# Leds.net
KiCad netlist of a schematic drawn in Altium Designer
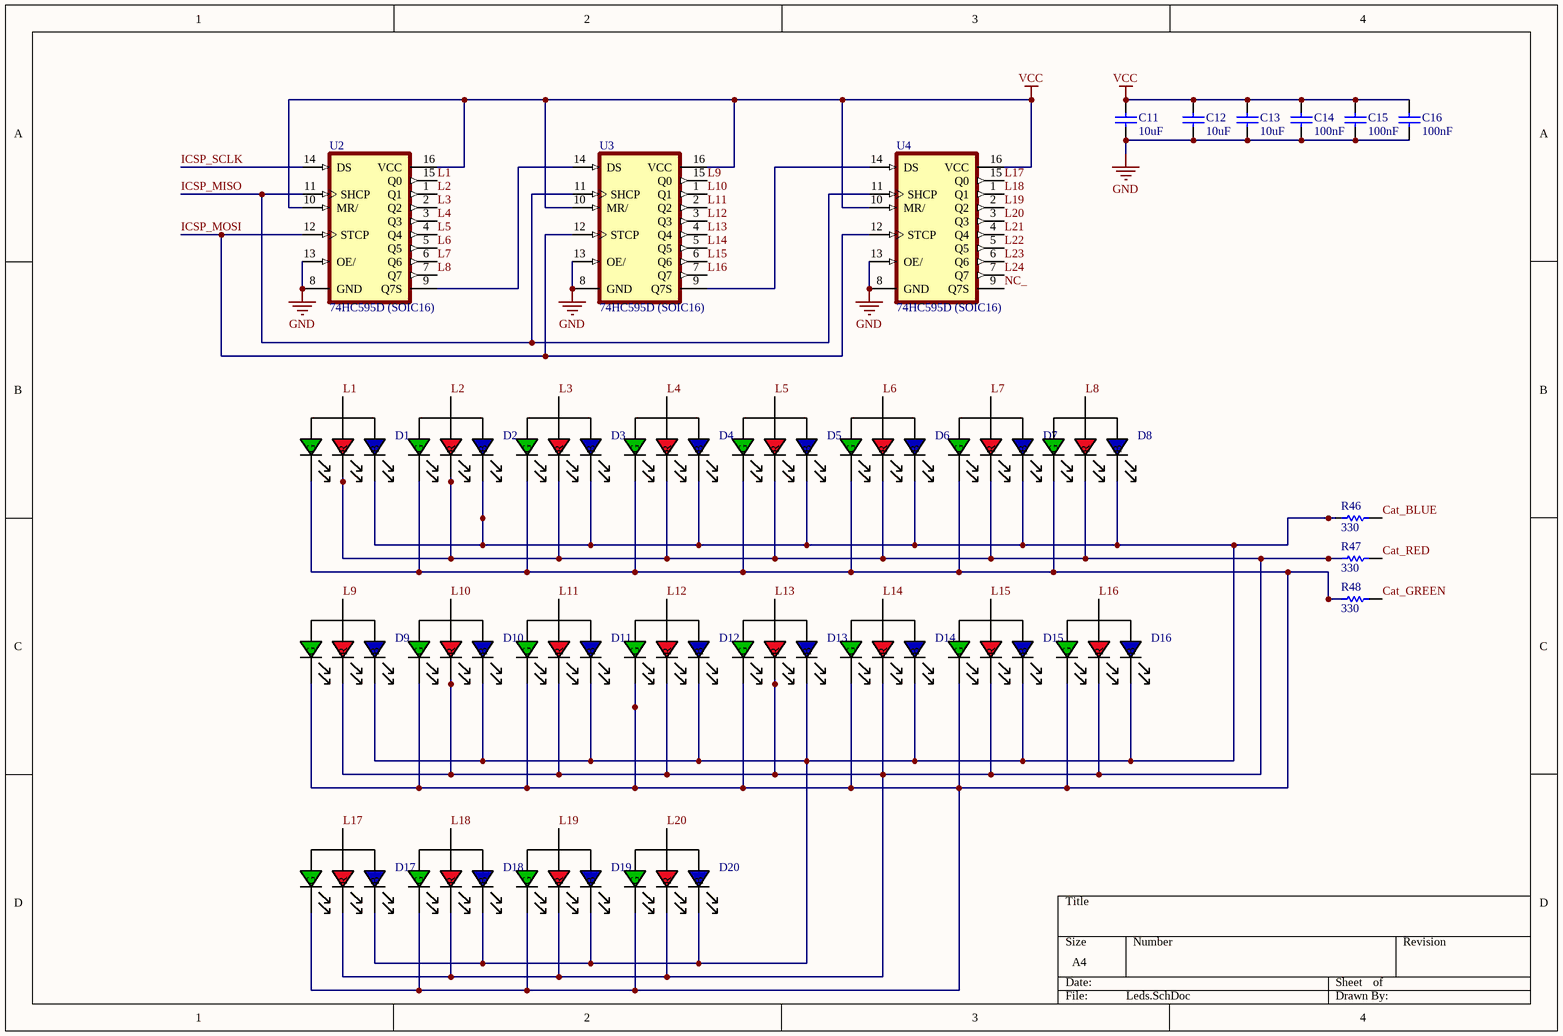
[diagram p0: Leds.SchDoc]

(export (version "E")
  (design (tool "Eeschema 10.0.6"))
  (components
    (comp (ref "C11")
      (value "10uF")
      (footprint "0603")
      (libsource (lib "LibDevs") (part "CAP 10uF 6.3V 20% 0603"))
    )
    (comp (ref "C12")
      (value "10uF")
      (footprint "0603")
      (libsource (lib "LibDevs") (part "CAP 10uF 6.3V 20% 0603"))
    )
    (comp (ref "C13")
      (value "10uF")
      (footprint "0603")
      (libsource (lib "LibDevs") (part "CAP 10uF 6.3V 20% 0603"))
    )
    (comp (ref "C14")
      (value "100nF")
      (footprint "0603")
      (libsource (lib "LibDevs") (part "CAP 100nF 10% 0603"))
    )
    (comp (ref "C15")
      (value "100nF")
      (footprint "0603")
      (libsource (lib "LibDevs") (part "CAP 100nF 10% 0603"))
    )
    (comp (ref "C16")
      (value "100nF")
      (footprint "0603")
      (libsource (lib "LibDevs") (part "CAP 100nF 10% 0603"))
    )
    (comp (ref "D1")
      (value "RGB LED CLEAR")
      (footprint "RADIAL 4 LEADS")
      (fields (field (name "MFR PART #") "TJ-L5FYTXHTCYLCRGB-AR") (field (name "LCSC PART #") "C330749"))
      (libsource (lib "LibDevs") (part "LED RGB TJ-L5FYTXHTCYLCRGB-AR"))
    )
    (comp (ref "D2")
      (value "RGB LED CLEAR")
      (footprint "RADIAL 4 LEADS")
      (fields (field (name "MFR PART #") "TJ-L5FYTXHTCYLCRGB-AR") (field (name "LCSC PART #") "C330749"))
      (libsource (lib "LibDevs") (part "LED RGB TJ-L5FYTXHTCYLCRGB-AR"))
    )
    (comp (ref "D3")
      (value "RGB LED CLEAR")
      (footprint "RADIAL 4 LEADS")
      (fields (field (name "MFR PART #") "TJ-L5FYTXHTCYLCRGB-AR") (field (name "LCSC PART #") "C330749"))
      (libsource (lib "LibDevs") (part "LED RGB TJ-L5FYTXHTCYLCRGB-AR"))
    )
    (comp (ref "D4")
      (value "RGB LED CLEAR")
      (footprint "RADIAL 4 LEADS")
      (fields (field (name "MFR PART #") "TJ-L5FYTXHTCYLCRGB-AR") (field (name "LCSC PART #") "C330749"))
      (libsource (lib "LibDevs") (part "LED RGB TJ-L5FYTXHTCYLCRGB-AR"))
    )
    (comp (ref "D5")
      (value "RGB LED CLEAR")
      (footprint "RADIAL 4 LEADS")
      (fields (field (name "MFR PART #") "TJ-L5FYTXHTCYLCRGB-AR") (field (name "LCSC PART #") "C330749"))
      (libsource (lib "LibDevs") (part "LED RGB TJ-L5FYTXHTCYLCRGB-AR"))
    )
    (comp (ref "D6")
      (value "RGB LED CLEAR")
      (footprint "RADIAL 4 LEADS")
      (fields (field (name "MFR PART #") "TJ-L5FYTXHTCYLCRGB-AR") (field (name "LCSC PART #") "C330749"))
      (libsource (lib "LibDevs") (part "LED RGB TJ-L5FYTXHTCYLCRGB-AR"))
    )
    (comp (ref "D7")
      (value "RGB LED CLEAR")
      (footprint "RADIAL 4 LEADS")
      (fields (field (name "MFR PART #") "TJ-L5FYTXHTCYLCRGB-AR") (field (name "LCSC PART #") "C330749"))
      (libsource (lib "LibDevs") (part "LED RGB TJ-L5FYTXHTCYLCRGB-AR"))
    )
    (comp (ref "D8")
      (value "RGB LED CLEAR")
      (footprint "RADIAL 4 LEADS")
      (fields (field (name "MFR PART #") "TJ-L5FYTXHTCYLCRGB-AR") (field (name "LCSC PART #") "C330749"))
      (libsource (lib "LibDevs") (part "LED RGB TJ-L5FYTXHTCYLCRGB-AR"))
    )
    (comp (ref "D9")
      (value "RGB LED CLEAR")
      (footprint "RADIAL 4 LEADS")
      (fields (field (name "MFR PART #") "TJ-L5FYTXHTCYLCRGB-AR") (field (name "LCSC PART #") "C330749"))
      (libsource (lib "LibDevs") (part "LED RGB TJ-L5FYTXHTCYLCRGB-AR"))
    )
    (comp (ref "D10")
      (value "RGB LED CLEAR")
      (footprint "RADIAL 4 LEADS")
      (fields (field (name "MFR PART #") "TJ-L5FYTXHTCYLCRGB-AR") (field (name "LCSC PART #") "C330749"))
      (libsource (lib "LibDevs") (part "LED RGB TJ-L5FYTXHTCYLCRGB-AR"))
    )
    (comp (ref "D11")
      (value "RGB LED CLEAR")
      (footprint "RADIAL 4 LEADS")
      (fields (field (name "MFR PART #") "TJ-L5FYTXHTCYLCRGB-AR") (field (name "LCSC PART #") "C330749"))
      (libsource (lib "LibDevs") (part "LED RGB TJ-L5FYTXHTCYLCRGB-AR"))
    )
    (comp (ref "D12")
      (value "RGB LED CLEAR")
      (footprint "RADIAL 4 LEADS")
      (fields (field (name "MFR PART #") "TJ-L5FYTXHTCYLCRGB-AR") (field (name "LCSC PART #") "C330749"))
      (libsource (lib "LibDevs") (part "LED RGB TJ-L5FYTXHTCYLCRGB-AR"))
    )
    (comp (ref "D13")
      (value "RGB LED CLEAR")
      (footprint "RADIAL 4 LEADS")
      (fields (field (name "MFR PART #") "TJ-L5FYTXHTCYLCRGB-AR") (field (name "LCSC PART #") "C330749"))
      (libsource (lib "LibDevs") (part "LED RGB TJ-L5FYTXHTCYLCRGB-AR"))
    )
    (comp (ref "D14")
      (value "RGB LED CLEAR")
      (footprint "RADIAL 4 LEADS")
      (fields (field (name "MFR PART #") "TJ-L5FYTXHTCYLCRGB-AR") (field (name "LCSC PART #") "C330749"))
      (libsource (lib "LibDevs") (part "LED RGB TJ-L5FYTXHTCYLCRGB-AR"))
    )
    (comp (ref "D15")
      (value "RGB LED CLEAR")
      (footprint "RADIAL 4 LEADS")
      (fields (field (name "MFR PART #") "TJ-L5FYTXHTCYLCRGB-AR") (field (name "LCSC PART #") "C330749"))
      (libsource (lib "LibDevs") (part "LED RGB TJ-L5FYTXHTCYLCRGB-AR"))
    )
    (comp (ref "D16")
      (value "RGB LED CLEAR")
      (footprint "RADIAL 4 LEADS")
      (fields (field (name "MFR PART #") "TJ-L5FYTXHTCYLCRGB-AR") (field (name "LCSC PART #") "C330749"))
      (libsource (lib "LibDevs") (part "LED RGB TJ-L5FYTXHTCYLCRGB-AR"))
    )
    (comp (ref "D17")
      (value "RGB LED CLEAR")
      (footprint "RADIAL 4 LEADS")
      (fields (field (name "MFR PART #") "TJ-L5FYTXHTCYLCRGB-AR") (field (name "LCSC PART #") "C330749"))
      (libsource (lib "LibDevs") (part "LED RGB TJ-L5FYTXHTCYLCRGB-AR"))
    )
    (comp (ref "D18")
      (value "RGB LED CLEAR")
      (footprint "RADIAL 4 LEADS")
      (fields (field (name "MFR PART #") "TJ-L5FYTXHTCYLCRGB-AR") (field (name "LCSC PART #") "C330749"))
      (libsource (lib "LibDevs") (part "LED RGB TJ-L5FYTXHTCYLCRGB-AR"))
    )
    (comp (ref "D19")
      (value "RGB LED CLEAR")
      (footprint "RADIAL 4 LEADS")
      (fields (field (name "MFR PART #") "TJ-L5FYTXHTCYLCRGB-AR") (field (name "LCSC PART #") "C330749"))
      (libsource (lib "LibDevs") (part "LED RGB TJ-L5FYTXHTCYLCRGB-AR"))
    )
    (comp (ref "D20")
      (value "RGB LED CLEAR")
      (footprint "RADIAL 4 LEADS")
      (fields (field (name "MFR PART #") "TJ-L5FYTXHTCYLCRGB-AR") (field (name "LCSC PART #") "C330749"))
      (libsource (lib "LibDevs") (part "LED RGB TJ-L5FYTXHTCYLCRGB-AR"))
    )
    (comp (ref "R46")
      (value "330")
      (footprint "0603")
      (fields (field (name "Comment") "RESISTOR GENERIC"))
      (libsource (lib "LibDevs") (part "RESISTOR GENERIC"))
    )
    (comp (ref "R47")
      (value "330")
      (footprint "0603")
      (fields (field (name "Comment") "RESISTOR GENERIC"))
      (libsource (lib "LibDevs") (part "RESISTOR GENERIC"))
    )
    (comp (ref "R48")
      (value "330")
      (footprint "0603")
      (fields (field (name "Comment") "RESISTOR GENERIC"))
      (libsource (lib "LibDevs") (part "RESISTOR GENERIC"))
    )
    (comp (ref "U2")
      (value "74HC595D (SOIC16)")
      (footprint "LibDevs:SOIC16-1.27-10X3.9MM")
      (description "Shift Shift Register 1 Element 8 Bit 16-SOP")
      (fields (field (name "MP") "74HC595D") (field (name "MF") "Toshiba"))
      (libsource (lib "LibDevs") (part "74HC595D (SOIC16)"))
    )
    (comp (ref "U3")
      (value "74HC595D (SOIC16)")
      (footprint "LibDevs:SOIC16-1.27-10X3.9MM")
      (description "Shift Shift Register 1 Element 8 Bit 16-SOP")
      (fields (field (name "MP") "74HC595D") (field (name "MF") "Toshiba"))
      (libsource (lib "LibDevs") (part "74HC595D (SOIC16)"))
    )
    (comp (ref "U4")
      (value "74HC595D (SOIC16)")
      (footprint "LibDevs:SOIC16-1.27-10X3.9MM")
      (description "Shift Shift Register 1 Element 8 Bit 16-SOP")
      (fields (field (name "MP") "74HC595D") (field (name "MF") "Toshiba"))
      (libsource (lib "LibDevs") (part "74HC595D (SOIC16)"))
    )
  )
  (nets
    (net (code "1") (name "/Cat_BLUE") (class "Default")
      (node (ref "R46") (pin "2") (pinfunction "2_2") (pintype "passive"))
    )
    (net (code "2") (name "/Cat_GREEN") (class "Default")
      (node (ref "R48") (pin "2") (pinfunction "2_2") (pintype "passive"))
    )
    (net (code "3") (name "/Cat_RED") (class "Default")
      (node (ref "R47") (pin "2") (pinfunction "2_2") (pintype "passive"))
    )
    (net (code "4") (name "/ICSP_MISO") (class "Default")
      (node (ref "U2") (pin "11") (pinfunction "SHCP_11") (pintype "input"))
      (node (ref "U3") (pin "11") (pinfunction "SHCP_11") (pintype "input"))
      (node (ref "U4") (pin "11") (pinfunction "SHCP_11") (pintype "input"))
    )
    (net (code "5") (name "/ICSP_MOSI") (class "Default")
      (node (ref "U2") (pin "12") (pinfunction "STCP_12") (pintype "input"))
      (node (ref "U3") (pin "12") (pinfunction "STCP_12") (pintype "input"))
      (node (ref "U4") (pin "12") (pinfunction "STCP_12") (pintype "input"))
    )
    (net (code "6") (name "/ICSP_SCLK") (class "Default")
      (node (ref "U2") (pin "14") (pinfunction "DS_14") (pintype "input"))
    )
    (net (code "7") (name "/L1") (class "Default")
      (node (ref "D1") (pin "2") (pinfunction "Anode_2") (pintype "passive"))
      (node (ref "U2") (pin "15") (pinfunction "Q0_15") (pintype "output"))
    )
    (net (code "8") (name "/L2") (class "Default")
      (node (ref "D2") (pin "2") (pinfunction "Anode_2") (pintype "passive"))
      (node (ref "U2") (pin "1") (pinfunction "Q1_1") (pintype "output"))
    )
    (net (code "9") (name "/L3") (class "Default")
      (node (ref "D3") (pin "2") (pinfunction "Anode_2") (pintype "passive"))
      (node (ref "U2") (pin "2") (pinfunction "Q2_2") (pintype "output"))
    )
    (net (code "10") (name "/L4") (class "Default")
      (node (ref "D4") (pin "2") (pinfunction "Anode_2") (pintype "passive"))
      (node (ref "U2") (pin "3") (pinfunction "Q3_3") (pintype "output"))
    )
    (net (code "11") (name "/L5") (class "Default")
      (node (ref "D5") (pin "2") (pinfunction "Anode_2") (pintype "passive"))
      (node (ref "U2") (pin "4") (pinfunction "Q4_4") (pintype "output"))
    )
    (net (code "12") (name "/L6") (class "Default")
      (node (ref "D6") (pin "2") (pinfunction "Anode_2") (pintype "passive"))
      (node (ref "U2") (pin "5") (pinfunction "Q5_5") (pintype "output"))
    )
    (net (code "13") (name "/L7") (class "Default")
      (node (ref "D7") (pin "2") (pinfunction "Anode_2") (pintype "passive"))
      (node (ref "U2") (pin "6") (pinfunction "Q6_6") (pintype "output"))
    )
    (net (code "14") (name "/L8") (class "Default")
      (node (ref "D8") (pin "2") (pinfunction "Anode_2") (pintype "passive"))
      (node (ref "U2") (pin "7") (pinfunction "Q7_7") (pintype "output"))
    )
    (net (code "15") (name "/L9") (class "Default")
      (node (ref "D9") (pin "2") (pinfunction "Anode_2") (pintype "passive"))
      (node (ref "U3") (pin "15") (pinfunction "Q0_15") (pintype "output"))
    )
    (net (code "16") (name "/L10") (class "Default")
      (node (ref "D10") (pin "2") (pinfunction "Anode_2") (pintype "passive"))
      (node (ref "U3") (pin "1") (pinfunction "Q1_1") (pintype "output"))
    )
    (net (code "17") (name "/L11") (class "Default")
      (node (ref "D11") (pin "2") (pinfunction "Anode_2") (pintype "passive"))
      (node (ref "U3") (pin "2") (pinfunction "Q2_2") (pintype "output"))
    )
    (net (code "18") (name "/L12") (class "Default")
      (node (ref "D12") (pin "2") (pinfunction "Anode_2") (pintype "passive"))
      (node (ref "U3") (pin "3") (pinfunction "Q3_3") (pintype "output"))
    )
    (net (code "19") (name "/L13") (class "Default")
      (node (ref "D13") (pin "2") (pinfunction "Anode_2") (pintype "passive"))
      (node (ref "U3") (pin "4") (pinfunction "Q4_4") (pintype "output"))
    )
    (net (code "20") (name "/L14") (class "Default")
      (node (ref "D14") (pin "2") (pinfunction "Anode_2") (pintype "passive"))
      (node (ref "U3") (pin "5") (pinfunction "Q5_5") (pintype "output"))
    )
    (net (code "21") (name "/L15") (class "Default")
      (node (ref "D15") (pin "2") (pinfunction "Anode_2") (pintype "passive"))
      (node (ref "U3") (pin "6") (pinfunction "Q6_6") (pintype "output"))
    )
    (net (code "22") (name "/L16") (class "Default")
      (node (ref "D16") (pin "2") (pinfunction "Anode_2") (pintype "passive"))
      (node (ref "U3") (pin "7") (pinfunction "Q7_7") (pintype "output"))
    )
    (net (code "23") (name "/L17") (class "Default")
      (node (ref "D17") (pin "2") (pinfunction "Anode_2") (pintype "passive"))
      (node (ref "U4") (pin "15") (pinfunction "Q0_15") (pintype "output"))
    )
    (net (code "24") (name "/L18") (class "Default")
      (node (ref "D18") (pin "2") (pinfunction "Anode_2") (pintype "passive"))
      (node (ref "U4") (pin "1") (pinfunction "Q1_1") (pintype "output"))
    )
    (net (code "25") (name "/L19") (class "Default")
      (node (ref "D19") (pin "2") (pinfunction "Anode_2") (pintype "passive"))
      (node (ref "U4") (pin "2") (pinfunction "Q2_2") (pintype "output"))
    )
    (net (code "26") (name "/L20") (class "Default")
      (node (ref "D20") (pin "2") (pinfunction "Anode_2") (pintype "passive"))
      (node (ref "U4") (pin "3") (pinfunction "Q3_3") (pintype "output"))
    )
    (net (code "27") (name "/L21") (class "Default")
      (node (ref "U4") (pin "4") (pinfunction "Q4_4") (pintype "output"))
    )
    (net (code "28") (name "/L22") (class "Default")
      (node (ref "U4") (pin "5") (pinfunction "Q5_5") (pintype "output"))
    )
    (net (code "29") (name "/L23") (class "Default")
      (node (ref "U4") (pin "6") (pinfunction "Q6_6") (pintype "output"))
    )
    (net (code "30") (name "/L24") (class "Default")
      (node (ref "U4") (pin "7") (pinfunction "Q7_7") (pintype "output"))
    )
    (net (code "31") (name "/NC_") (class "Default")
      (node (ref "U4") (pin "9") (pinfunction "Q7S_9") (pintype "passive"))
    )
    (net (code "32") (name "GND") (class "Default")
      (node (ref "C11") (pin "1") (pinfunction "1_1") (pintype "passive"))
      (node (ref "C12") (pin "1") (pinfunction "1_1") (pintype "passive"))
      (node (ref "C13") (pin "1") (pinfunction "1_1") (pintype "passive"))
      (node (ref "C14") (pin "1") (pinfunction "1_1") (pintype "passive"))
      (node (ref "C15") (pin "1") (pinfunction "1_1") (pintype "passive"))
      (node (ref "C16") (pin "1") (pinfunction "1_1") (pintype "passive"))
      (node (ref "U2") (pin "13") (pinfunction "OE/_13") (pintype "input"))
      (node (ref "U2") (pin "8") (pinfunction "GND_8") (pintype "power_in"))
      (node (ref "U3") (pin "13") (pinfunction "OE/_13") (pintype "input"))
      (node (ref "U3") (pin "8") (pinfunction "GND_8") (pintype "power_in"))
      (node (ref "U4") (pin "13") (pinfunction "OE/_13") (pintype "input"))
      (node (ref "U4") (pin "8") (pinfunction "GND_8") (pintype "power_in"))
    )
    (net (code "33") (name "Net-(D1-B)") (class "Default")
      (node (ref "D1") (pin "4") (pinfunction "B_4") (pintype "passive"))
      (node (ref "D10") (pin "4") (pinfunction "B_4") (pintype "passive"))
      (node (ref "D11") (pin "4") (pinfunction "B_4") (pintype "passive"))
      (node (ref "D12") (pin "4") (pinfunction "B_4") (pintype "passive"))
      (node (ref "D13") (pin "4") (pinfunction "B_4") (pintype "passive"))
      (node (ref "D14") (pin "4") (pinfunction "B_4") (pintype "passive"))
      (node (ref "D15") (pin "4") (pinfunction "B_4") (pintype "passive"))
      (node (ref "D16") (pin "4") (pinfunction "B_4") (pintype "passive"))
      (node (ref "D17") (pin "4") (pinfunction "B_4") (pintype "passive"))
      (node (ref "D18") (pin "4") (pinfunction "B_4") (pintype "passive"))
      (node (ref "D19") (pin "4") (pinfunction "B_4") (pintype "passive"))
      (node (ref "D2") (pin "4") (pinfunction "B_4") (pintype "passive"))
      (node (ref "D20") (pin "4") (pinfunction "B_4") (pintype "passive"))
      (node (ref "D3") (pin "4") (pinfunction "B_4") (pintype "passive"))
      (node (ref "D4") (pin "4") (pinfunction "B_4") (pintype "passive"))
      (node (ref "D5") (pin "4") (pinfunction "B_4") (pintype "passive"))
      (node (ref "D6") (pin "4") (pinfunction "B_4") (pintype "passive"))
      (node (ref "D7") (pin "4") (pinfunction "B_4") (pintype "passive"))
      (node (ref "D8") (pin "4") (pinfunction "B_4") (pintype "passive"))
      (node (ref "D9") (pin "4") (pinfunction "B_4") (pintype "passive"))
      (node (ref "R46") (pin "1") (pinfunction "1_1") (pintype "passive"))
    )
    (net (code "34") (name "Net-(D1-G)") (class "Default")
      (node (ref "D1") (pin "3") (pinfunction "G_3") (pintype "passive"))
      (node (ref "D10") (pin "3") (pinfunction "G_3") (pintype "passive"))
      (node (ref "D11") (pin "3") (pinfunction "G_3") (pintype "passive"))
      (node (ref "D12") (pin "3") (pinfunction "G_3") (pintype "passive"))
      (node (ref "D13") (pin "3") (pinfunction "G_3") (pintype "passive"))
      (node (ref "D14") (pin "3") (pinfunction "G_3") (pintype "passive"))
      (node (ref "D15") (pin "3") (pinfunction "G_3") (pintype "passive"))
      (node (ref "D16") (pin "3") (pinfunction "G_3") (pintype "passive"))
      (node (ref "D17") (pin "3") (pinfunction "G_3") (pintype "passive"))
      (node (ref "D18") (pin "3") (pinfunction "G_3") (pintype "passive"))
      (node (ref "D19") (pin "3") (pinfunction "G_3") (pintype "passive"))
      (node (ref "D2") (pin "3") (pinfunction "G_3") (pintype "passive"))
      (node (ref "D20") (pin "3") (pinfunction "G_3") (pintype "passive"))
      (node (ref "D3") (pin "3") (pinfunction "G_3") (pintype "passive"))
      (node (ref "D4") (pin "3") (pinfunction "G_3") (pintype "passive"))
      (node (ref "D5") (pin "3") (pinfunction "G_3") (pintype "passive"))
      (node (ref "D6") (pin "3") (pinfunction "G_3") (pintype "passive"))
      (node (ref "D7") (pin "3") (pinfunction "G_3") (pintype "passive"))
      (node (ref "D8") (pin "3") (pinfunction "G_3") (pintype "passive"))
      (node (ref "D9") (pin "3") (pinfunction "G_3") (pintype "passive"))
      (node (ref "R48") (pin "1") (pinfunction "1_1") (pintype "passive"))
    )
    (net (code "35") (name "Net-(D1-R)") (class "Default")
      (node (ref "D1") (pin "1") (pinfunction "R_1") (pintype "passive"))
      (node (ref "D10") (pin "1") (pinfunction "R_1") (pintype "passive"))
      (node (ref "D11") (pin "1") (pinfunction "R_1") (pintype "passive"))
      (node (ref "D12") (pin "1") (pinfunction "R_1") (pintype "passive"))
      (node (ref "D13") (pin "1") (pinfunction "R_1") (pintype "passive"))
      (node (ref "D14") (pin "1") (pinfunction "R_1") (pintype "passive"))
      (node (ref "D15") (pin "1") (pinfunction "R_1") (pintype "passive"))
      (node (ref "D16") (pin "1") (pinfunction "R_1") (pintype "passive"))
      (node (ref "D17") (pin "1") (pinfunction "R_1") (pintype "passive"))
      (node (ref "D18") (pin "1") (pinfunction "R_1") (pintype "passive"))
      (node (ref "D19") (pin "1") (pinfunction "R_1") (pintype "passive"))
      (node (ref "D2") (pin "1") (pinfunction "R_1") (pintype "passive"))
      (node (ref "D20") (pin "1") (pinfunction "R_1") (pintype "passive"))
      (node (ref "D3") (pin "1") (pinfunction "R_1") (pintype "passive"))
      (node (ref "D4") (pin "1") (pinfunction "R_1") (pintype "passive"))
      (node (ref "D5") (pin "1") (pinfunction "R_1") (pintype "passive"))
      (node (ref "D6") (pin "1") (pinfunction "R_1") (pintype "passive"))
      (node (ref "D7") (pin "1") (pinfunction "R_1") (pintype "passive"))
      (node (ref "D8") (pin "1") (pinfunction "R_1") (pintype "passive"))
      (node (ref "D9") (pin "1") (pinfunction "R_1") (pintype "passive"))
      (node (ref "R47") (pin "1") (pinfunction "1_1") (pintype "passive"))
    )
    (net (code "36") (name "Net-(U2-Q7S)") (class "Default")
      (node (ref "U2") (pin "9") (pinfunction "Q7S_9") (pintype "passive"))
      (node (ref "U3") (pin "14") (pinfunction "DS_14") (pintype "input"))
    )
    (net (code "37") (name "Net-(U3-Q7S)") (class "Default")
      (node (ref "U3") (pin "9") (pinfunction "Q7S_9") (pintype "passive"))
      (node (ref "U4") (pin "14") (pinfunction "DS_14") (pintype "input"))
    )
    (net (code "38") (name "VCC") (class "Default")
      (node (ref "C11") (pin "2") (pinfunction "2_2") (pintype "passive"))
      (node (ref "C12") (pin "2") (pinfunction "2_2") (pintype "passive"))
      (node (ref "C13") (pin "2") (pinfunction "2_2") (pintype "passive"))
      (node (ref "C14") (pin "2") (pinfunction "2_2") (pintype "passive"))
      (node (ref "C15") (pin "2") (pinfunction "2_2") (pintype "passive"))
      (node (ref "C16") (pin "2") (pinfunction "2_2") (pintype "passive"))
      (node (ref "U2") (pin "10") (pinfunction "MR/_10") (pintype "input"))
      (node (ref "U2") (pin "16") (pinfunction "VCC_16") (pintype "power_in"))
      (node (ref "U3") (pin "10") (pinfunction "MR/_10") (pintype "input"))
      (node (ref "U3") (pin "16") (pinfunction "VCC_16") (pintype "power_in"))
      (node (ref "U4") (pin "10") (pinfunction "MR/_10") (pintype "input"))
      (node (ref "U4") (pin "16") (pinfunction "VCC_16") (pintype "power_in"))
    )
  )
)
